# Alimentacao.net
KiCad netlist of a schematic drawn in Altium Designer
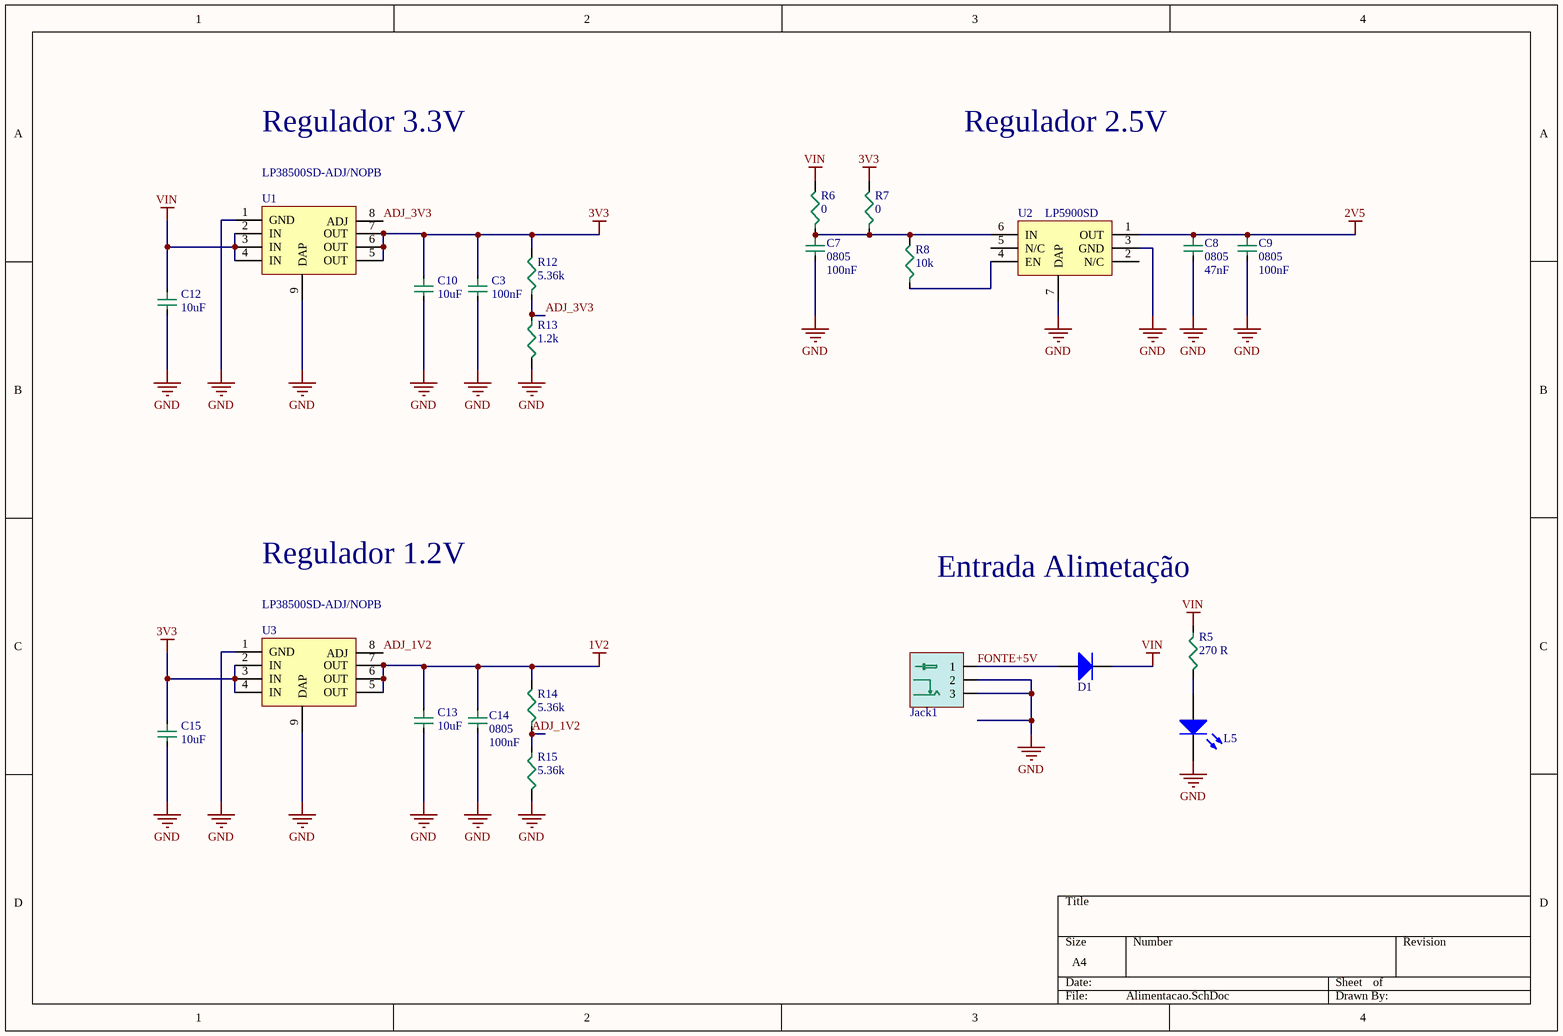
[diagram p0: Alimentacao.SchDoc]

(export (version "E")
  (design (tool "Eeschema 10.0.6"))
  (components
    (comp (ref "C3")
      (value "100nF")
      (footprint "0603C")
      (description "Capacitor SMD 0603")
      (fields (field (name "Comment") "0603"))
      (libsource (lib "RLC_Integrated_Library") (part "Capacitor SMD 0603"))
    )
    (comp (ref "C7")
      (value "0805")
      (footprint "0603C")
      (description "Capacitor SMD 0603")
      (fields (field (name "ALTIUM_VALUE") "100nF"))
      (libsource (lib "RLC_Integrated_Library") (part "Capacitor SMD 0603"))
    )
    (comp (ref "C8")
      (value "0805")
      (footprint "0603C")
      (description "Capacitor SMD 0603")
      (fields (field (name "ALTIUM_VALUE") "47nF"))
      (libsource (lib "RLC_Integrated_Library") (part "Capacitor SMD 0603"))
    )
    (comp (ref "C9")
      (value "0805")
      (footprint "0603C")
      (description "Capacitor SMD 0603")
      (fields (field (name "ALTIUM_VALUE") "100nF"))
      (libsource (lib "RLC_Integrated_Library") (part "Capacitor SMD 0603"))
    )
    (comp (ref "C10")
      (value "10uF")
      (footprint "0603C")
      (description "Capacitor SMD 0603")
      (fields (field (name "Comment") "0603"))
      (libsource (lib "RLC_Integrated_Library") (part "Capacitor SMD 0603"))
    )
    (comp (ref "C12")
      (value "10uF")
      (footprint "0603C")
      (description "Capacitor SMD 0603")
      (fields (field (name "Comment") "0603"))
      (libsource (lib "RLC_Integrated_Library") (part "Capacitor SMD 0603"))
    )
    (comp (ref "C13")
      (value "10uF")
      (footprint "0603C")
      (description "Capacitor SMD 0603")
      (fields (field (name "Comment") "0603"))
      (libsource (lib "RLC_Integrated_Library") (part "Capacitor SMD 0603"))
    )
    (comp (ref "C14")
      (value "0805")
      (footprint "0603C")
      (description "Capacitor SMD 0603")
      (fields (field (name "ALTIUM_VALUE") "100nF"))
      (libsource (lib "RLC_Integrated_Library") (part "Capacitor SMD 0603"))
    )
    (comp (ref "C15")
      (value "10uF")
      (footprint "0603C")
      (description "Capacitor SMD 0603")
      (fields (field (name "Comment") "0603"))
      (libsource (lib "RLC_Integrated_Library") (part "Capacitor SMD 0603"))
    )
    (comp (ref "D1")
      (value "Diodo_1")
      (footprint "SOD123")
      (description "DIODE SCHOTTKY 20V 0.5A SOD123")
      (libsource (lib "Schlib1") (part "Diodo_1"))
    )
    (comp (ref "Jack1")
      (value "DC Supply Jack")
      (footprint "CON_DC_POWER_JACK")
      (libsource (lib "Miscellaneous_Connectors_Integrated_Library") (part "DC_Power_connector"))
    )
    (comp (ref "L5")
      (value "LED 0805")
      (footprint "LED SMD 0603")
      (description "Typical INFRARED GaAs LED")
      (fields (field (name "PUBLISHER") "Altium Limited"))
      (libsource (lib "Diodo_Transistor_Integrated_Library") (part "LED 0603 SMD"))
    )
    (comp (ref "R5")
      (value "270 R")
      (footprint "0603")
      (description "Resistor SMD 0603 1/10 W")
      (fields (field (name "Comment") "0805"))
      (libsource (lib "RLC_Integrated_Library") (part "Resistor SMD 0603 1/10 W"))
    )
    (comp (ref "R6")
      (value "0")
      (footprint "0603")
      (description "Resistor SMD 0603 1/10 W")
      (fields (field (name "Comment") "0805"))
      (libsource (lib "RLC_Integrated_Library") (part "Resistor SMD 0603 1/10 W"))
    )
    (comp (ref "R7")
      (value "0")
      (footprint "0603")
      (description "Resistor SMD 0603 1/10 W")
      (fields (field (name "Comment") "0805"))
      (libsource (lib "RLC_Integrated_Library") (part "Resistor SMD 0603 1/10 W"))
    )
    (comp (ref "R8")
      (value "10k")
      (footprint "0603")
      (description "Resistor SMD 0603 1/10 W")
      (fields (field (name "Comment") "0805"))
      (libsource (lib "RLC_Integrated_Library") (part "Resistor SMD 0603 1/10 W"))
    )
    (comp (ref "R12")
      (value "5.36k")
      (footprint "0603")
      (description "Resistor SMD 0603 1/10 W")
      (fields (field (name "Comment") "0805"))
      (libsource (lib "RLC_Integrated_Library") (part "Resistor SMD 0603 1/10 W"))
    )
    (comp (ref "R13")
      (value "1.2k")
      (footprint "0603")
      (description "Resistor SMD 0603 1/10 W")
      (fields (field (name "Comment") "0805"))
      (libsource (lib "RLC_Integrated_Library") (part "Resistor SMD 0603 1/10 W"))
    )
    (comp (ref "R14")
      (value "5.36k")
      (footprint "0603")
      (description "Resistor SMD 0603 1/10 W")
      (fields (field (name "Comment") "0805"))
      (libsource (lib "RLC_Integrated_Library") (part "Resistor SMD 0603 1/10 W"))
    )
    (comp (ref "R15")
      (value "5.36k")
      (footprint "0603")
      (description "Resistor SMD 0603 1/10 W")
      (fields (field (name "Comment") "0805"))
      (libsource (lib "RLC_Integrated_Library") (part "Resistor SMD 0603 1/10 W"))
    )
    (comp (ref "U1")
      (value "LP38500SD-ADJ/NOPB")
      (footprint "8-WFDFN")
      (description "1.5-A Flexcap Low-Dropout Linear Regulator")
      (fields (field (name "PUBLISHER") "Altium Limited"))
      (libsource (lib "CI_Integrated_Library") (part "LP38500SD-ADJ/NOPB"))
    )
    (comp (ref "U2")
      (value "LP5900SD")
      (footprint "6-WFDFN")
      (description "1.5-A Flexcap Low-Dropout Linear Regulator")
      (fields (field (name "PUBLISHER") "Altium Limited"))
      (libsource (lib "CI_Integrated_Library") (part "LP5900SD-2.5/NOPB"))
    )
    (comp (ref "U3")
      (value "LP38500SD-ADJ/NOPB")
      (footprint "8-WFDFN")
      (description "1.5-A Flexcap Low-Dropout Linear Regulator")
      (fields (field (name "PUBLISHER") "Altium Limited"))
      (libsource (lib "CI_Integrated_Library") (part "LP38500SD-ADJ/NOPB"))
    )
  )
  (nets
    (net (code "1") (name "/ADJ_1V2") (class "Default")
      (node (ref "R14") (pin "1") (pinfunction "1_1") (pintype "passive"))
      (node (ref "R15") (pin "1") (pinfunction "1_1") (pintype "passive"))
      (node (ref "U3") (pin "8") (pinfunction "ADJ_8") (pintype "power_in"))
    )
    (net (code "2") (name "/ADJ_3V3") (class "Default")
      (node (ref "R12") (pin "1") (pinfunction "1_1") (pintype "passive"))
      (node (ref "R13") (pin "1") (pinfunction "1_1") (pintype "passive"))
      (node (ref "U1") (pin "8") (pinfunction "ADJ_8") (pintype "power_in"))
    )
    (net (code "3") (name "/FONTE+5V") (class "Default")
      (node (ref "D1") (pin "1") (pinfunction "A_1") (pintype "passive"))
      (node (ref "Jack1") (pin "1") (pinfunction "1_1") (pintype "passive"))
    )
    (net (code "4") (name "1V2") (class "Default")
      (node (ref "C13") (pin "1") (pinfunction "1_1") (pintype "passive"))
      (node (ref "C14") (pin "1") (pinfunction "1_1") (pintype "passive"))
      (node (ref "R14") (pin "2") (pinfunction "2_2") (pintype "passive"))
      (node (ref "U3") (pin "5") (pinfunction "OUT_5") (pintype "power_in"))
      (node (ref "U3") (pin "6") (pinfunction "OUT_6") (pintype "power_in"))
      (node (ref "U3") (pin "7") (pinfunction "OUT_7") (pintype "power_in"))
    )
    (net (code "5") (name "2V5") (class "Default")
      (node (ref "C8") (pin "1") (pinfunction "1_1") (pintype "passive"))
      (node (ref "C9") (pin "1") (pinfunction "1_1") (pintype "passive"))
      (node (ref "U2") (pin "1") (pinfunction "OUT_1") (pintype "power_in"))
    )
    (net (code "6") (name "3V3") (class "Default")
      (node (ref "C10") (pin "1") (pinfunction "1_1") (pintype "passive"))
      (node (ref "C15") (pin "1") (pinfunction "1_1") (pintype "passive"))
      (node (ref "C3") (pin "1") (pinfunction "1_1") (pintype "passive"))
      (node (ref "R12") (pin "2") (pinfunction "2_2") (pintype "passive"))
      (node (ref "R7") (pin "2") (pinfunction "2_2") (pintype "passive"))
      (node (ref "U1") (pin "5") (pinfunction "OUT_5") (pintype "power_in"))
      (node (ref "U1") (pin "6") (pinfunction "OUT_6") (pintype "power_in"))
      (node (ref "U1") (pin "7") (pinfunction "OUT_7") (pintype "power_in"))
      (node (ref "U3") (pin "2") (pinfunction "IN_2") (pintype "power_in"))
      (node (ref "U3") (pin "3") (pinfunction "IN_3") (pintype "power_in"))
      (node (ref "U3") (pin "4") (pinfunction "IN_4") (pintype "power_in"))
    )
    (net (code "7") (name "GND") (class "Default")
      (node (ref "C10") (pin "2") (pinfunction "2_2") (pintype "passive"))
      (node (ref "C12") (pin "2") (pinfunction "2_2") (pintype "passive"))
      (node (ref "C13") (pin "2") (pinfunction "2_2") (pintype "passive"))
      (node (ref "C14") (pin "2") (pinfunction "2_2") (pintype "passive"))
      (node (ref "C15") (pin "2") (pinfunction "2_2") (pintype "passive"))
      (node (ref "C3") (pin "2") (pinfunction "2_2") (pintype "passive"))
      (node (ref "C7") (pin "2") (pinfunction "2_2") (pintype "passive"))
      (node (ref "C8") (pin "2") (pinfunction "2_2") (pintype "passive"))
      (node (ref "C9") (pin "2") (pinfunction "2_2") (pintype "passive"))
      (node (ref "Jack1") (pin "2") (pinfunction "2_2") (pintype "passive"))
      (node (ref "Jack1") (pin "3") (pinfunction "3_3") (pintype "passive"))
      (node (ref "L5") (pin "2") (pinfunction "K_2") (pintype "passive"))
      (node (ref "R13") (pin "2") (pinfunction "2_2") (pintype "passive"))
      (node (ref "R15") (pin "2") (pinfunction "2_2") (pintype "passive"))
      (node (ref "U1") (pin "1") (pinfunction "GND_1") (pintype "power_in"))
      (node (ref "U1") (pin "9") (pinfunction "DAP_9") (pintype "power_in"))
      (node (ref "U2") (pin "3") (pinfunction "GND_3") (pintype "power_in"))
      (node (ref "U2") (pin "7") (pinfunction "DAP_7") (pintype "power_in"))
      (node (ref "U3") (pin "1") (pinfunction "GND_1") (pintype "power_in"))
      (node (ref "U3") (pin "9") (pinfunction "DAP_9") (pintype "power_in"))
    )
    (net (code "8") (name "Net-(L5-A)") (class "Default")
      (node (ref "L5") (pin "1") (pinfunction "A_1") (pintype "passive"))
      (node (ref "R5") (pin "2") (pinfunction "2_2") (pintype "passive"))
    )
    (net (code "9") (name "Net-(U2-EN)") (class "Default")
      (node (ref "R8") (pin "1") (pinfunction "1_1") (pintype "passive"))
      (node (ref "U2") (pin "4") (pinfunction "EN_4") (pintype "power_in"))
    )
    (net (code "10") (name "Net-(U2-IN)") (class "Default")
      (node (ref "C7") (pin "1") (pinfunction "1_1") (pintype "passive"))
      (node (ref "R6") (pin "1") (pinfunction "1_1") (pintype "passive"))
      (node (ref "R7") (pin "1") (pinfunction "1_1") (pintype "passive"))
      (node (ref "R8") (pin "2") (pinfunction "2_2") (pintype "passive"))
      (node (ref "U2") (pin "6") (pinfunction "IN_6") (pintype "power_in"))
    )
    (net (code "11") (name "VIN") (class "Default")
      (node (ref "C12") (pin "1") (pinfunction "1_1") (pintype "passive"))
      (node (ref "D1") (pin "2") (pinfunction "K_2") (pintype "passive"))
      (node (ref "R5") (pin "1") (pinfunction "1_1") (pintype "passive"))
      (node (ref "R6") (pin "2") (pinfunction "2_2") (pintype "passive"))
      (node (ref "U1") (pin "2") (pinfunction "IN_2") (pintype "power_in"))
      (node (ref "U1") (pin "3") (pinfunction "IN_3") (pintype "power_in"))
      (node (ref "U1") (pin "4") (pinfunction "IN_4") (pintype "power_in"))
    )
    (net (code "12") (name "unconnected-(U2-N{slash}C-Pad2)") (class "Default")
      (node (ref "U2") (pin "2") (pinfunction "N/C_2") (pintype "power_in"))
    )
    (net (code "13") (name "unconnected-(U2-N{slash}C-Pad5)") (class "Default")
      (node (ref "U2") (pin "5") (pinfunction "N/C_5") (pintype "power_in"))
    )
  )
)
